# SCH_AI-driven-Air-Quality-Forecasting-Mo.net
KiCad netlist of a schematic drawn in EasyEDA
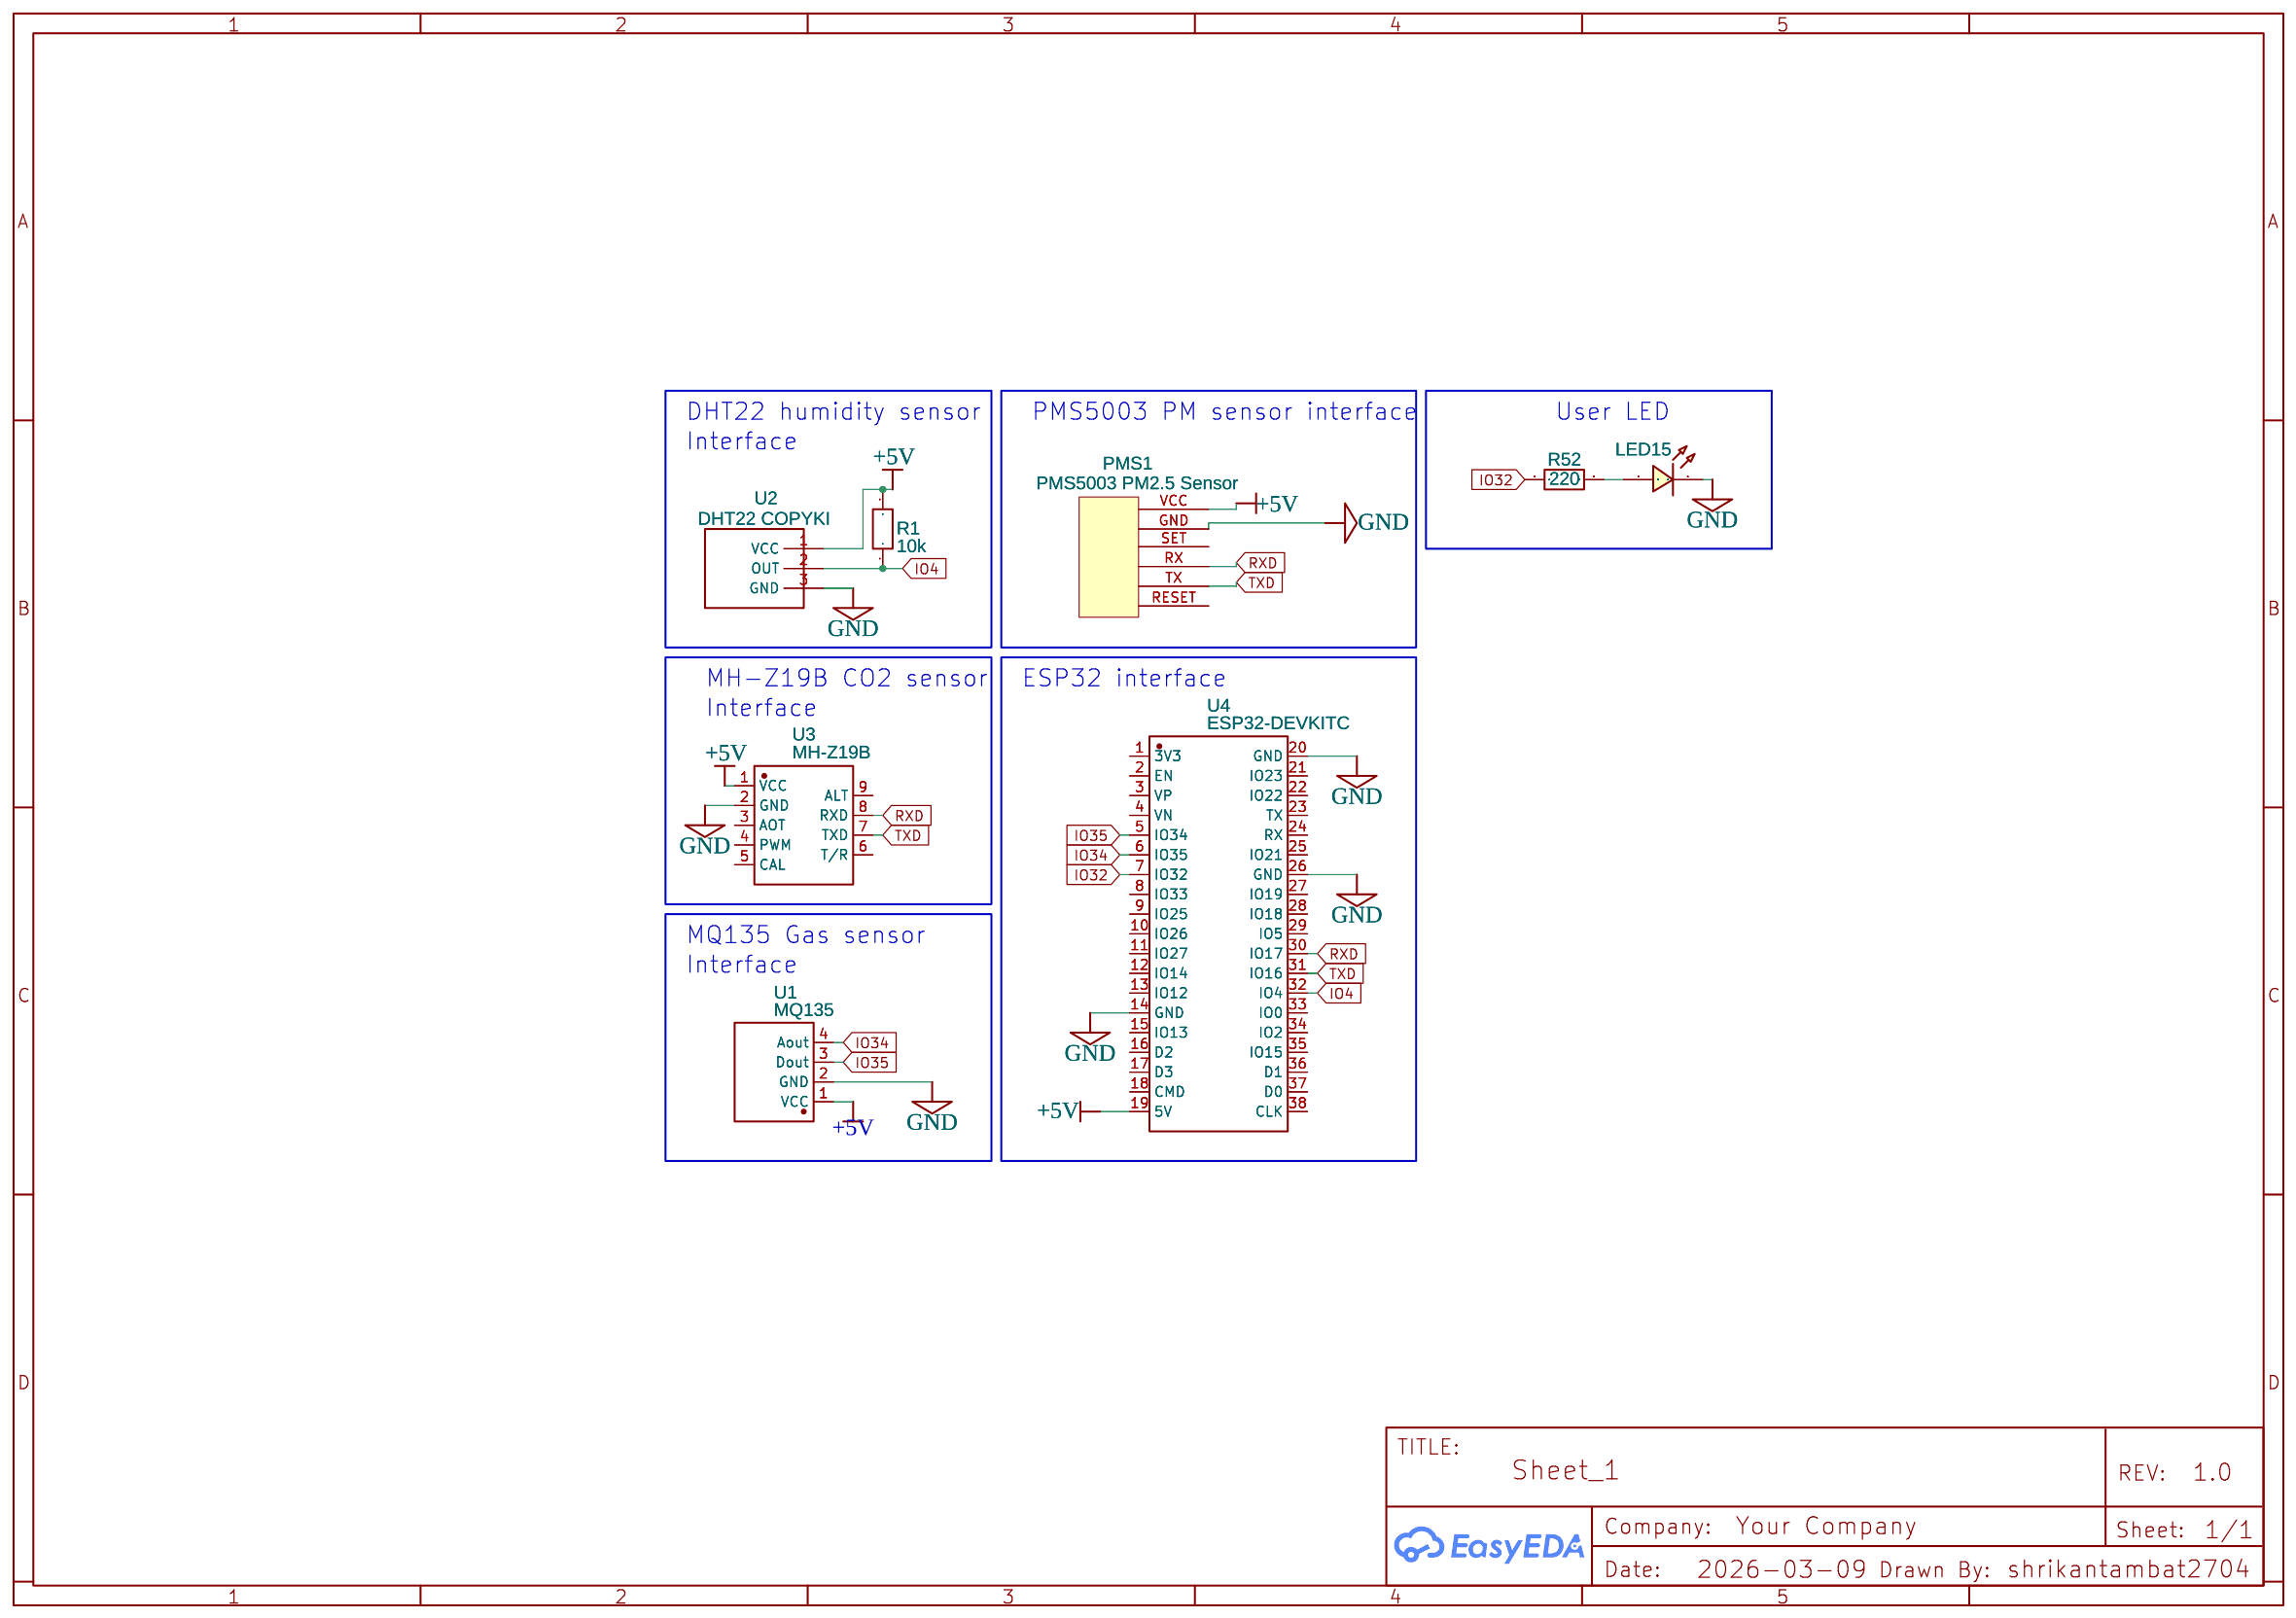
[diagram p0: schematic sheet]

(export (version "E")
  (design (tool "Eeschema 10.0.6"))
  (components
    (comp (ref "LED15")
      (value "LED-0805_R")
      (fields
        (field (name "Manufacturer Part") "17-21SURC/S530-A3/TR8")
        (field (name "Manufacturer") "EVERLIGHT(台湾亿光)")
      )
      (libsource (lib "") (part "LED-0805_R"))
    )
    (comp (ref "PMS1") (value "PMS5003 PM2.5 Sensor") (libsource (lib "") (part "PMS5003 PM2.5 Sensor")))
    (comp (ref "R1") (value "10k") (libsource (lib "") (part "R_AXIAL-0.4_EU")))
    (comp (ref "R52") (value "220") (libsource (lib "") (part "R_0805_EU")))
    (comp (ref "U1") (value "MQ135") (libsource (lib "") (part "MQ135")))
    (comp (ref "U2") (value "DHT22 COPYKI") (libsource (lib "") (part "DHT22 COPYKI")))
    (comp (ref "U3")
      (value "MH-Z19B")
      (fields (field (name "Manufacturer Part") "SY-CO2-28BMI") (field (name "Manufacturer") "saiya(赛亚)"))
      (libsource (lib "") (part "SY-CO2-MH1001A"))
    )
    (comp (ref "U4")
      (value "ESP32-DEVKITC")
      (fields
        (field (name "Manufacturer Part") "ESP32-DevKitC")
        (field (name "Manufacturer") "ESPRESSIF(乐鑫)")
      )
      (libsource (lib "") (part "ESP32-DEVKITC"))
    )
  )
  (nets
    (net (code "1") (name "+5V") (class "Default")
      (node (ref "PMS1") (pin "VCC") (pintype "unspecified"))
      (node (ref "R1") (pin "2") (pinfunction "2_2") (pintype "unspecified"))
      (node (ref "U1") (pin "1") (pinfunction "VCC_1") (pintype "unspecified"))
      (node (ref "U2") (pin "1") (pinfunction "VCC_1") (pintype "unspecified"))
      (node (ref "U3") (pin "1") (pinfunction "VCC_1") (pintype "unspecified"))
      (node (ref "U4") (pin "19") (pinfunction "5V_19") (pintype "unspecified"))
    )
    (net (code "2") (name "GND") (class "Default")
      (node (ref "LED15") (pin "2") (pinfunction "2_2") (pintype "unspecified"))
      (node (ref "PMS1") (pin "GND") (pintype "unspecified"))
      (node (ref "U1") (pin "2") (pinfunction "GND_2") (pintype "unspecified"))
      (node (ref "U2") (pin "3") (pinfunction "GND_3") (pintype "unspecified"))
      (node (ref "U3") (pin "2") (pinfunction "GND_2") (pintype "unspecified"))
      (node (ref "U4") (pin "14") (pinfunction "GND_14") (pintype "unspecified"))
      (node (ref "U4") (pin "20") (pinfunction "GND_20") (pintype "unspecified"))
      (node (ref "U4") (pin "26") (pinfunction "GND_26") (pintype "unspecified"))
    )
    (net (code "3") (name "IO4") (class "Default")
      (node (ref "R1") (pin "1") (pinfunction "1_1") (pintype "unspecified"))
      (node (ref "U2") (pin "2") (pinfunction "OUT_2") (pintype "unspecified"))
      (node (ref "U4") (pin "32") (pinfunction "IO4_32") (pintype "unspecified"))
    )
    (net (code "4") (name "IO32") (class "Default")
      (node (ref "R52") (pin "1") (pinfunction "1_1") (pintype "unspecified"))
      (node (ref "U4") (pin "7") (pinfunction "IO32_7") (pintype "unspecified"))
    )
    (net (code "5") (name "IO34") (class "Default")
      (node (ref "U1") (pin "4") (pinfunction "Aout_4") (pintype "unspecified"))
      (node (ref "U4") (pin "6") (pinfunction "IO35_6") (pintype "unspecified"))
    )
    (net (code "6") (name "IO35") (class "Default")
      (node (ref "U1") (pin "3") (pinfunction "Dout_3") (pintype "unspecified"))
      (node (ref "U4") (pin "5") (pinfunction "IO34_5") (pintype "unspecified"))
    )
    (net (code "7") (name "Net-(LED15-Pad1)") (class "Default")
      (node (ref "LED15") (pin "1") (pinfunction "1_1") (pintype "unspecified"))
      (node (ref "R52") (pin "2") (pinfunction "2_2") (pintype "unspecified"))
    )
    (net (code "8") (name "RXD") (class "Default")
      (node (ref "PMS1") (pin "RX") (pintype "unspecified"))
      (node (ref "U3") (pin "8") (pinfunction "RXD_8") (pintype "unspecified"))
      (node (ref "U4") (pin "30") (pinfunction "IO17_30") (pintype "unspecified"))
    )
    (net (code "9") (name "TXD") (class "Default")
      (node (ref "PMS1") (pin "TX") (pintype "unspecified"))
      (node (ref "U3") (pin "7") (pinfunction "TXD_7") (pintype "unspecified"))
      (node (ref "U4") (pin "31") (pinfunction "IO16_31") (pintype "unspecified"))
    )
    (net (code "10") (name "unconnected-(PMS1-PadRESET)") (class "Default")
      (node (ref "PMS1") (pin "RESET") (pintype "unspecified"))
    )
    (net (code "11") (name "unconnected-(PMS1-PadSET)") (class "Default")
      (node (ref "PMS1") (pin "SET") (pintype "unspecified"))
    )
    (net (code "12") (name "unconnected-(U3-ALT-Pad9)") (class "Default")
      (node (ref "U3") (pin "9") (pinfunction "ALT_9") (pintype "unspecified"))
    )
    (net (code "13") (name "unconnected-(U3-AOT-Pad3)") (class "Default")
      (node (ref "U3") (pin "3") (pinfunction "AOT_3") (pintype "unspecified"))
    )
    (net (code "14") (name "unconnected-(U3-CAL-Pad5)") (class "Default")
      (node (ref "U3") (pin "5") (pinfunction "CAL_5") (pintype "unspecified"))
    )
    (net (code "15") (name "unconnected-(U3-PWM-Pad4)") (class "Default")
      (node (ref "U3") (pin "4") (pinfunction "PWM_4") (pintype "unspecified"))
    )
    (net (code "16") (name "unconnected-(U3-T{slash}R-Pad6)") (class "Default")
      (node (ref "U3") (pin "6") (pinfunction "T/R_6") (pintype "unspecified"))
    )
    (net (code "17") (name "unconnected-(U4-3V3-Pad1)") (class "Default")
      (node (ref "U4") (pin "1") (pinfunction "3V3_1") (pintype "unspecified"))
    )
    (net (code "18") (name "unconnected-(U4-CLK-Pad38)") (class "Default")
      (node (ref "U4") (pin "38") (pinfunction "CLK_38") (pintype "unspecified"))
    )
    (net (code "19") (name "unconnected-(U4-CMD-Pad18)") (class "Default")
      (node (ref "U4") (pin "18") (pinfunction "CMD_18") (pintype "unspecified"))
    )
    (net (code "20") (name "unconnected-(U4-D0-Pad37)") (class "Default")
      (node (ref "U4") (pin "37") (pinfunction "D0_37") (pintype "unspecified"))
    )
    (net (code "21") (name "unconnected-(U4-D1-Pad36)") (class "Default")
      (node (ref "U4") (pin "36") (pinfunction "D1_36") (pintype "unspecified"))
    )
    (net (code "22") (name "unconnected-(U4-D2-Pad16)") (class "Default")
      (node (ref "U4") (pin "16") (pinfunction "D2_16") (pintype "unspecified"))
    )
    (net (code "23") (name "unconnected-(U4-D3-Pad17)") (class "Default")
      (node (ref "U4") (pin "17") (pinfunction "D3_17") (pintype "unspecified"))
    )
    (net (code "24") (name "unconnected-(U4-EN-Pad2)") (class "Default")
      (node (ref "U4") (pin "2") (pinfunction "EN_2") (pintype "unspecified"))
    )
    (net (code "25") (name "unconnected-(U4-IO0-Pad33)") (class "Default")
      (node (ref "U4") (pin "33") (pinfunction "IO0_33") (pintype "unspecified"))
    )
    (net (code "26") (name "unconnected-(U4-IO2-Pad34)") (class "Default")
      (node (ref "U4") (pin "34") (pinfunction "IO2_34") (pintype "unspecified"))
    )
    (net (code "27") (name "unconnected-(U4-IO5-Pad29)") (class "Default")
      (node (ref "U4") (pin "29") (pinfunction "IO5_29") (pintype "unspecified"))
    )
    (net (code "28") (name "unconnected-(U4-IO12-Pad13)") (class "Default")
      (node (ref "U4") (pin "13") (pinfunction "IO12_13") (pintype "unspecified"))
    )
    (net (code "29") (name "unconnected-(U4-IO13-Pad15)") (class "Default")
      (node (ref "U4") (pin "15") (pinfunction "IO13_15") (pintype "unspecified"))
    )
    (net (code "30") (name "unconnected-(U4-IO14-Pad12)") (class "Default")
      (node (ref "U4") (pin "12") (pinfunction "IO14_12") (pintype "unspecified"))
    )
    (net (code "31") (name "unconnected-(U4-IO15-Pad35)") (class "Default")
      (node (ref "U4") (pin "35") (pinfunction "IO15_35") (pintype "unspecified"))
    )
    (net (code "32") (name "unconnected-(U4-IO18-Pad28)") (class "Default")
      (node (ref "U4") (pin "28") (pinfunction "IO18_28") (pintype "unspecified"))
    )
    (net (code "33") (name "unconnected-(U4-IO19-Pad27)") (class "Default")
      (node (ref "U4") (pin "27") (pinfunction "IO19_27") (pintype "unspecified"))
    )
    (net (code "34") (name "unconnected-(U4-IO21-Pad25)") (class "Default")
      (node (ref "U4") (pin "25") (pinfunction "IO21_25") (pintype "unspecified"))
    )
    (net (code "35") (name "unconnected-(U4-IO22-Pad22)") (class "Default")
      (node (ref "U4") (pin "22") (pinfunction "IO22_22") (pintype "unspecified"))
    )
    (net (code "36") (name "unconnected-(U4-IO23-Pad21)") (class "Default")
      (node (ref "U4") (pin "21") (pinfunction "IO23_21") (pintype "unspecified"))
    )
    (net (code "37") (name "unconnected-(U4-IO25-Pad9)") (class "Default")
      (node (ref "U4") (pin "9") (pinfunction "IO25_9") (pintype "unspecified"))
    )
    (net (code "38") (name "unconnected-(U4-IO26-Pad10)") (class "Default")
      (node (ref "U4") (pin "10") (pinfunction "IO26_10") (pintype "unspecified"))
    )
    (net (code "39") (name "unconnected-(U4-IO27-Pad11)") (class "Default")
      (node (ref "U4") (pin "11") (pinfunction "IO27_11") (pintype "unspecified"))
    )
    (net (code "40") (name "unconnected-(U4-IO33-Pad8)") (class "Default")
      (node (ref "U4") (pin "8") (pinfunction "IO33_8") (pintype "unspecified"))
    )
    (net (code "41") (name "unconnected-(U4-RX-Pad24)") (class "Default")
      (node (ref "U4") (pin "24") (pinfunction "RX_24") (pintype "unspecified"))
    )
    (net (code "42") (name "unconnected-(U4-TX-Pad23)") (class "Default")
      (node (ref "U4") (pin "23") (pinfunction "TX_23") (pintype "unspecified"))
    )
    (net (code "43") (name "unconnected-(U4-VN-Pad4)") (class "Default")
      (node (ref "U4") (pin "4") (pinfunction "VN_4") (pintype "unspecified"))
    )
    (net (code "44") (name "unconnected-(U4-VP-Pad3)") (class "Default")
      (node (ref "U4") (pin "3") (pinfunction "VP_3") (pintype "unspecified"))
    )
  )
)
